# LTC3105.net
KiCad netlist of a schematic drawn in EAGLE
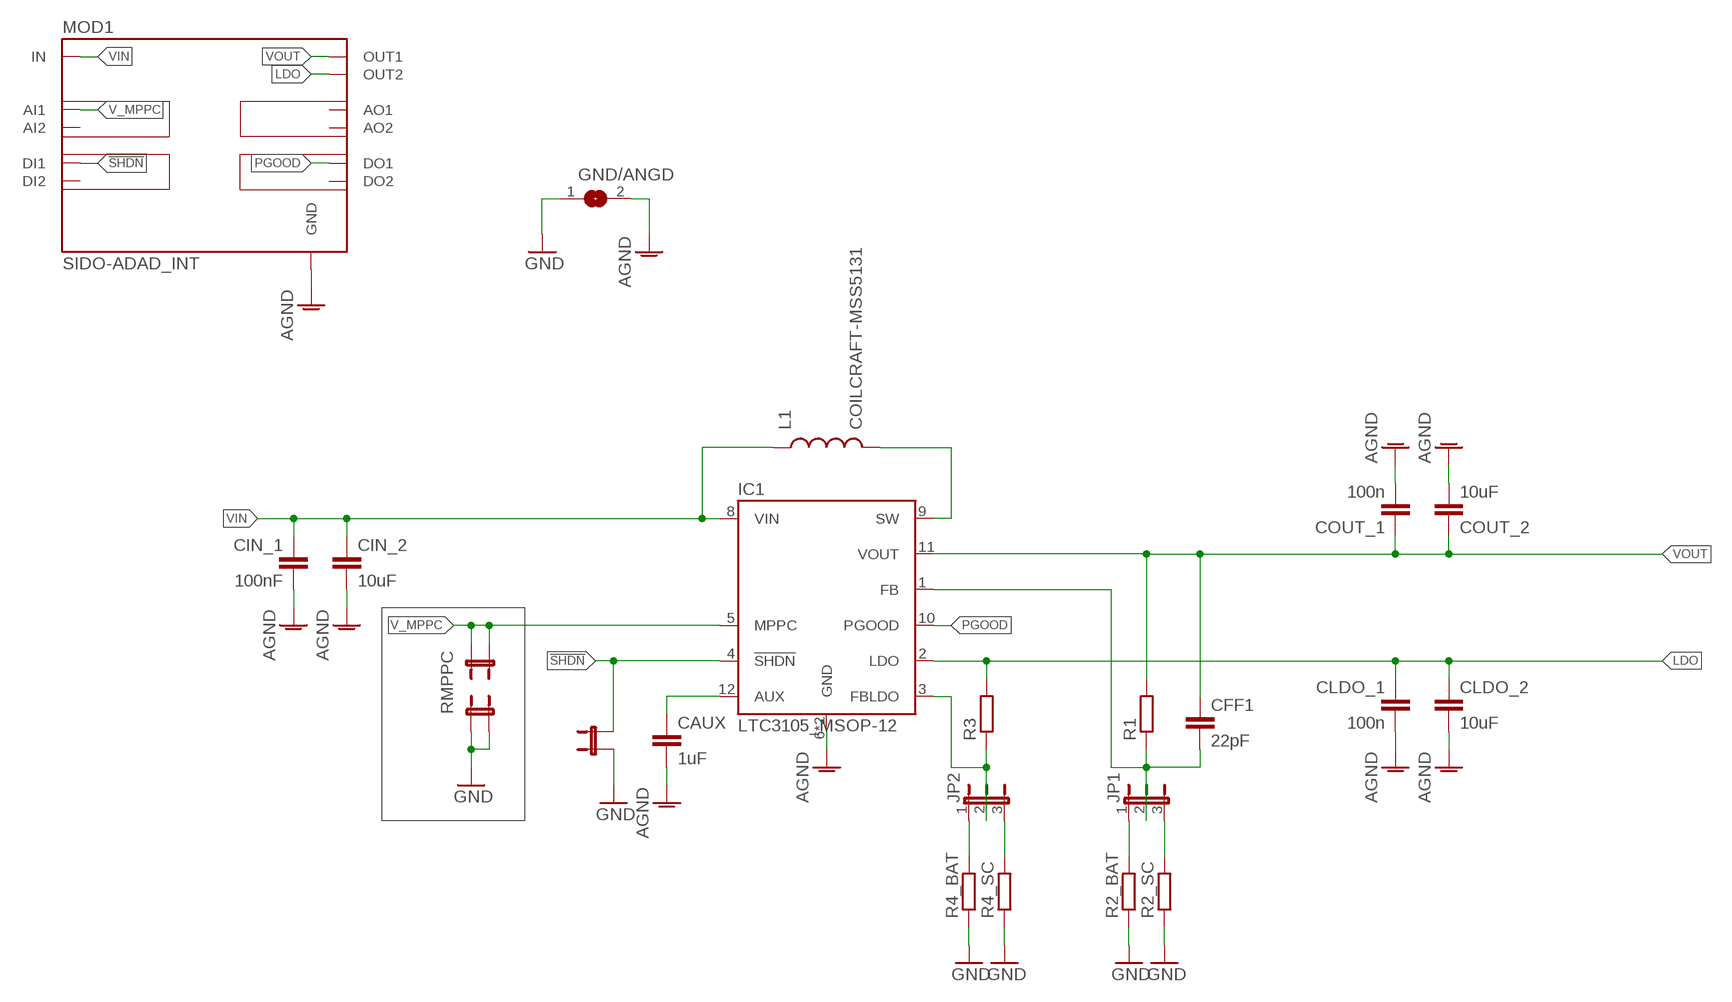
[diagram p0: schematic, sheet 1]

(export (version "E")
  (design (tool "Eeschema 10.0.6"))
  (components
    (comp (ref "CAUX")
      (value "1uF")
      (footprint "eagle-import:C0805K")
      (libsource (lib "eagle-import") (part "C-EUC0805K"))
    )
    (comp (ref "CFF1")
      (value "22pF")
      (footprint "eagle-import:C0805K")
      (libsource (lib "eagle-import") (part "C-EUC0805K"))
    )
    (comp (ref "CIN_1")
      (value "100nF")
      (footprint "eagle-import:C0805K")
      (libsource (lib "eagle-import") (part "C-EUC0805K"))
    )
    (comp (ref "CIN_2")
      (value "10uF")
      (footprint "eagle-import:C0805K")
      (libsource (lib "eagle-import") (part "C-EUC0805K"))
    )
    (comp (ref "CLDO_1")
      (value "100n")
      (footprint "eagle-import:C0805K")
      (libsource (lib "eagle-import") (part "C-EUC0805K"))
    )
    (comp (ref "CLDO_2")
      (value "10uF")
      (footprint "eagle-import:C0805K")
      (libsource (lib "eagle-import") (part "C-EUC0805K"))
    )
    (comp (ref "COUT_1")
      (value "100n")
      (footprint "eagle-import:C0805K")
      (libsource (lib "eagle-import") (part "C-EUC0805K"))
    )
    (comp (ref "COUT_2")
      (value "10uF")
      (footprint "eagle-import:C0805K")
      (libsource (lib "eagle-import") (part "C-EUC0805K"))
    )
    (comp (ref "GND/ANGD")
      (value "SJ")
      (footprint "eagle-import:SJ")
      (libsource (lib "eagle-import") (part "SJ"))
    )
    (comp (ref "IC1")
      (value "LTC3105_MSOP-12")
      (footprint "eagle-import:MSOP-12")
      (libsource (lib "eagle-import") (part "LTC3105_MSOP-12"))
    )
    (comp (ref "JP1")
      (value "JP2E")
      (footprint "eagle-import:JP2")
      (libsource (lib "eagle-import") (part "JP2E"))
    )
    (comp (ref "JP2")
      (value "JP2E")
      (footprint "eagle-import:JP2")
      (libsource (lib "eagle-import") (part "JP2E"))
    )
    (comp (ref "JP3")
      (value "JP2_SMALL_PAD")
      (footprint "eagle-import:JP2_SMALL_PAD")
      (libsource (lib "eagle-import") (part "JP2_SMALL_PAD"))
    )
    (comp (ref "JP4")
      (value "JP2_SMALL_PAD")
      (footprint "eagle-import:JP2_SMALL_PAD")
      (libsource (lib "eagle-import") (part "JP2_SMALL_PAD"))
    )
    (comp (ref "JP5")
      (value "JP2_SMALL_PAD")
      (footprint "eagle-import:JP2_SMALL_PAD")
      (libsource (lib "eagle-import") (part "JP2_SMALL_PAD"))
    )
    (comp (ref "L1")
      (value "COILCRAFT-MSS5131")
      (footprint "eagle-import:COILCRAFT_MSS5131")
      (libsource (lib "eagle-import") (part "COILCRAFT-MSS5131"))
    )
    (comp (ref "MOD1")
      (value "SIDO-ADAD_INT")
      (footprint "eagle-import:SIDO-ADAD")
      (libsource (lib "eagle-import") (part "SIDO-ADAD_INT"))
    )
    (comp (ref "R1")
      (value "R-EU_R0805")
      (footprint "eagle-import:R0805")
      (libsource (lib "eagle-import") (part "R-EU_R0805"))
    )
    (comp (ref "R2_BAT")
      (value "R-EU_R0805")
      (footprint "eagle-import:R0805")
      (libsource (lib "eagle-import") (part "R-EU_R0805"))
    )
    (comp (ref "R2_SC")
      (value "R-EU_R0805")
      (footprint "eagle-import:R0805")
      (libsource (lib "eagle-import") (part "R-EU_R0805"))
    )
    (comp (ref "R3")
      (value "R-EU_R0805")
      (footprint "eagle-import:R0805")
      (libsource (lib "eagle-import") (part "R-EU_R0805"))
    )
    (comp (ref "R4_BAT")
      (value "R-EU_R0805")
      (footprint "eagle-import:R0805")
      (libsource (lib "eagle-import") (part "R-EU_R0805"))
    )
    (comp (ref "R4_SC")
      (value "R-EU_R0805")
      (footprint "eagle-import:R0805")
      (libsource (lib "eagle-import") (part "R-EU_R0805"))
    )
  )
  (nets
    (net (code "1") (name "/~{SHDN}") (class "Default")
      (node (ref "IC1") (pin "4") (pinfunction "~{SHDN}_4") (pintype "input"))
      (node (ref "JP5") (pin "2") (pinfunction "2_2") (pintype "passive"))
      (node (ref "MOD1") (pin "DI1") (pinfunction "DI1_DI1") (pintype "output"))
    )
    (net (code "2") (name "AGND") (class "Default")
      (node (ref "CAUX") (pin "2") (pinfunction "2_2") (pintype "passive"))
      (node (ref "CIN_1") (pin "2") (pinfunction "2_2") (pintype "passive"))
      (node (ref "CIN_2") (pin "2") (pinfunction "2_2") (pintype "passive"))
      (node (ref "CLDO_1") (pin "2") (pinfunction "2_2") (pintype "passive"))
      (node (ref "CLDO_2") (pin "2") (pinfunction "2_2") (pintype "passive"))
      (node (ref "COUT_1") (pin "2") (pinfunction "2_2") (pintype "passive"))
      (node (ref "COUT_2") (pin "2") (pinfunction "2_2") (pintype "passive"))
      (node (ref "GND/ANGD") (pin "2") (pinfunction "2_2") (pintype "passive"))
      (node (ref "IC1") (pin "6") (pinfunction "GND_6") (pintype "power_in"))
      (node (ref "IC1") (pin "7") (pinfunction "GND_7") (pintype "power_in"))
      (node (ref "MOD1") (pin "GND1") (pinfunction "GND_GND1") (pintype "power_in"))
      (node (ref "MOD1") (pin "GND2") (pinfunction "GND_GND2") (pintype "power_in"))
      (node (ref "MOD1") (pin "GND3") (pinfunction "GND_GND3") (pintype "power_in"))
      (node (ref "MOD1") (pin "GND4") (pinfunction "GND_GND4") (pintype "power_in"))
    )
    (net (code "3") (name "GND") (class "Default")
      (node (ref "GND/ANGD") (pin "1") (pinfunction "1_1") (pintype "passive"))
      (node (ref "JP4") (pin "1") (pinfunction "1_1") (pintype "passive"))
      (node (ref "JP4") (pin "2") (pinfunction "2_2") (pintype "passive"))
      (node (ref "JP5") (pin "1") (pinfunction "1_1") (pintype "passive"))
      (node (ref "R2_BAT") (pin "1") (pinfunction "1_1") (pintype "passive"))
      (node (ref "R2_SC") (pin "1") (pinfunction "1_1") (pintype "passive"))
      (node (ref "R4_BAT") (pin "1") (pinfunction "1_1") (pintype "passive"))
      (node (ref "R4_SC") (pin "1") (pinfunction "1_1") (pintype "passive"))
    )
    (net (code "4") (name "LDO") (class "Default")
      (node (ref "CLDO_1") (pin "1") (pinfunction "1_1") (pintype "passive"))
      (node (ref "CLDO_2") (pin "1") (pinfunction "1_1") (pintype "passive"))
      (node (ref "IC1") (pin "2") (pinfunction "LDO_2") (pintype "power_in"))
      (node (ref "MOD1") (pin "OUT2_1") (pinfunction "OUT2_OUT2_1") (pintype "input"))
      (node (ref "MOD1") (pin "OUT2_2") (pinfunction "OUT2_OUT2_2") (pintype "input"))
      (node (ref "MOD1") (pin "OUT2_3") (pinfunction "OUT2_OUT2_3") (pintype "input"))
      (node (ref "MOD1") (pin "OUT2_4") (pinfunction "OUT2_OUT2_4") (pintype "input"))
      (node (ref "R3") (pin "2") (pinfunction "2_2") (pintype "passive"))
    )
    (net (code "5") (name "Net-(IC1-AUX)") (class "Default")
      (node (ref "CAUX") (pin "1") (pinfunction "1_1") (pintype "passive"))
      (node (ref "IC1") (pin "12") (pinfunction "AUX_12") (pintype "passive"))
    )
    (net (code "6") (name "Net-(IC1-FB)") (class "Default")
      (node (ref "CFF1") (pin "2") (pinfunction "2_2") (pintype "passive"))
      (node (ref "IC1") (pin "1") (pinfunction "FB_1") (pintype "input"))
      (node (ref "JP1") (pin "2") (pinfunction "2_2") (pintype "passive"))
      (node (ref "R1") (pin "1") (pinfunction "1_1") (pintype "passive"))
    )
    (net (code "7") (name "Net-(IC1-FBLDO)") (class "Default")
      (node (ref "IC1") (pin "3") (pinfunction "FBLDO_3") (pintype "input"))
      (node (ref "JP2") (pin "2") (pinfunction "2_2") (pintype "passive"))
      (node (ref "R3") (pin "1") (pinfunction "1_1") (pintype "passive"))
    )
    (net (code "8") (name "Net-(IC1-SW)") (class "Default")
      (node (ref "IC1") (pin "9") (pinfunction "SW_9") (pintype "passive"))
      (node (ref "L1") (pin "P$1") (pinfunction "2_P$1") (pintype "passive"))
    )
    (net (code "9") (name "Net-(JP1-Pad1)") (class "Default")
      (node (ref "JP1") (pin "1") (pinfunction "1_1") (pintype "passive"))
      (node (ref "R2_BAT") (pin "2") (pinfunction "2_2") (pintype "passive"))
    )
    (net (code "10") (name "Net-(JP1-Pad3)") (class "Default")
      (node (ref "JP1") (pin "3") (pinfunction "3_3") (pintype "passive"))
      (node (ref "R2_SC") (pin "2") (pinfunction "2_2") (pintype "passive"))
    )
    (net (code "11") (name "Net-(JP2-Pad1)") (class "Default")
      (node (ref "JP2") (pin "1") (pinfunction "1_1") (pintype "passive"))
      (node (ref "R4_BAT") (pin "2") (pinfunction "2_2") (pintype "passive"))
    )
    (net (code "12") (name "Net-(JP2-Pad3)") (class "Default")
      (node (ref "JP2") (pin "3") (pinfunction "3_3") (pintype "passive"))
      (node (ref "R4_SC") (pin "2") (pinfunction "2_2") (pintype "passive"))
    )
    (net (code "13") (name "PGOOD") (class "Default")
      (node (ref "IC1") (pin "10") (pinfunction "PGOOD_10") (pintype "output"))
      (node (ref "MOD1") (pin "DO1") (pinfunction "DO1_DO1") (pintype "input"))
    )
    (net (code "14") (name "VIN") (class "Default")
      (node (ref "CIN_1") (pin "1") (pinfunction "1_1") (pintype "passive"))
      (node (ref "CIN_2") (pin "1") (pinfunction "1_1") (pintype "passive"))
      (node (ref "IC1") (pin "8") (pinfunction "VIN_8") (pintype "power_in"))
      (node (ref "L1") (pin "P$2") (pinfunction "1_P$2") (pintype "passive"))
      (node (ref "MOD1") (pin "IN1") (pinfunction "IN_IN1") (pintype "output"))
      (node (ref "MOD1") (pin "IN2") (pinfunction "IN_IN2") (pintype "output"))
      (node (ref "MOD1") (pin "IN3") (pinfunction "IN_IN3") (pintype "output"))
      (node (ref "MOD1") (pin "IN4") (pinfunction "IN_IN4") (pintype "output"))
    )
    (net (code "15") (name "VOUT") (class "Default")
      (node (ref "CFF1") (pin "1") (pinfunction "1_1") (pintype "passive"))
      (node (ref "COUT_1") (pin "1") (pinfunction "1_1") (pintype "passive"))
      (node (ref "COUT_2") (pin "1") (pinfunction "1_1") (pintype "passive"))
      (node (ref "IC1") (pin "11") (pinfunction "VOUT_11") (pintype "power_in"))
      (node (ref "MOD1") (pin "OUT1_1") (pinfunction "OUT1_OUT1_1") (pintype "input"))
      (node (ref "MOD1") (pin "OUT1_2") (pinfunction "OUT1_OUT1_2") (pintype "input"))
      (node (ref "MOD1") (pin "OUT1_3") (pinfunction "OUT1_OUT1_3") (pintype "input"))
      (node (ref "MOD1") (pin "OUT1_4") (pinfunction "OUT1_OUT1_4") (pintype "input"))
      (node (ref "R1") (pin "2") (pinfunction "2_2") (pintype "passive"))
    )
    (net (code "16") (name "V_MPPC") (class "Default")
      (node (ref "IC1") (pin "5") (pinfunction "MPPC_5") (pintype "input"))
      (node (ref "JP3") (pin "1") (pinfunction "1_1") (pintype "passive"))
      (node (ref "JP3") (pin "2") (pinfunction "2_2") (pintype "passive"))
      (node (ref "MOD1") (pin "AI1") (pinfunction "AI1_AI1") (pintype "output"))
    )
    (net (code "17") (name "unconnected-(MOD1-PadAI2)") (class "Default")
      (node (ref "MOD1") (pin "AI2") (pinfunction "AI2_AI2") (pintype "output"))
    )
    (net (code "18") (name "unconnected-(MOD1-PadAO1)") (class "Default")
      (node (ref "MOD1") (pin "AO1") (pinfunction "AO1_AO1") (pintype "input"))
    )
    (net (code "19") (name "unconnected-(MOD1-PadAO2)") (class "Default")
      (node (ref "MOD1") (pin "AO2") (pinfunction "AO2_AO2") (pintype "input"))
    )
    (net (code "20") (name "unconnected-(MOD1-PadDI2)") (class "Default")
      (node (ref "MOD1") (pin "DI2") (pinfunction "DI2_DI2") (pintype "output"))
    )
    (net (code "21") (name "unconnected-(MOD1-PadDO2)") (class "Default")
      (node (ref "MOD1") (pin "DO2") (pinfunction "DO2_DO2") (pintype "input"))
    )
  )
)
